# currentsense.net
KiCad netlist of a schematic drawn in EAGLE
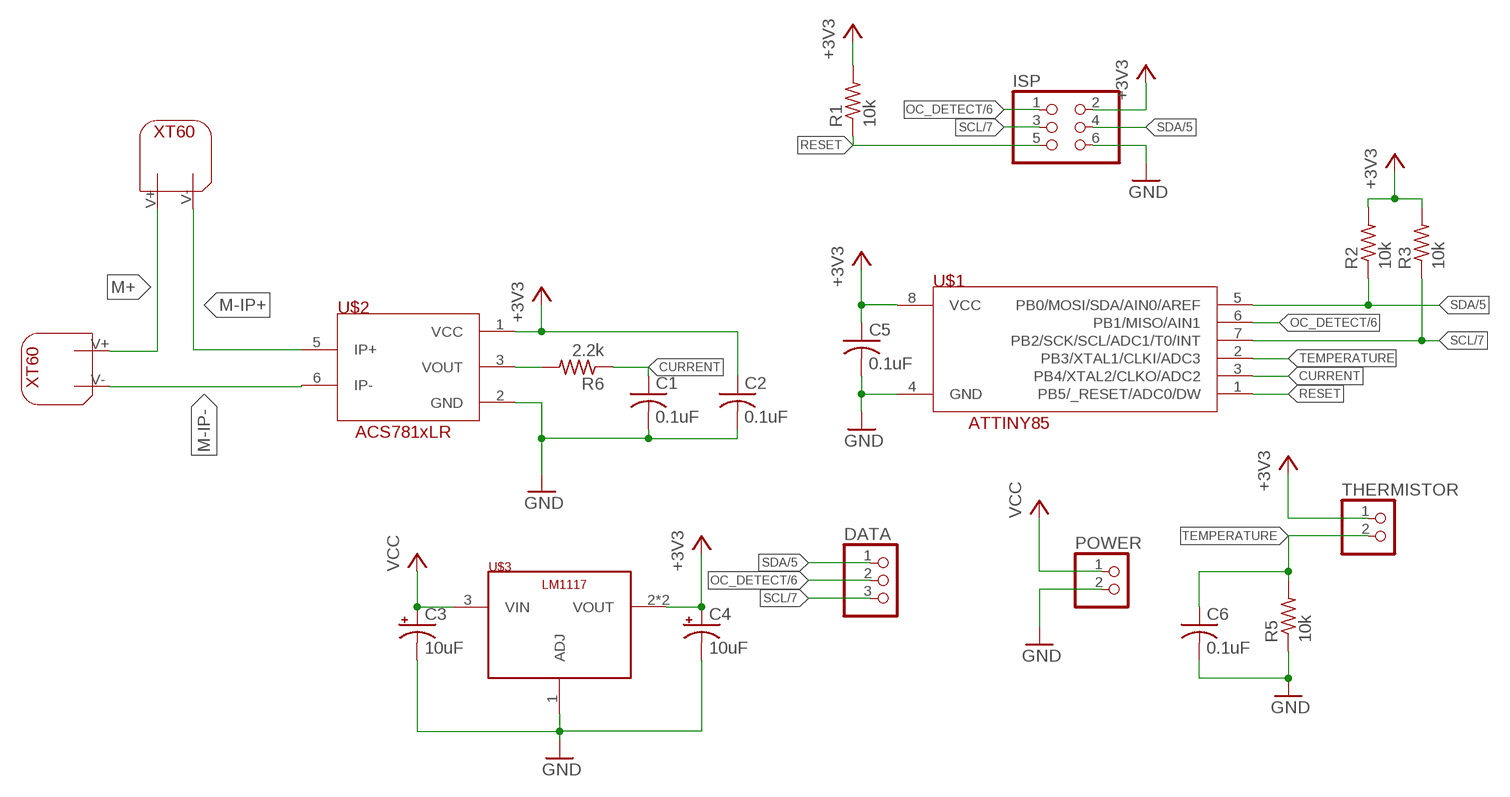
[diagram p0: schematic, sheet 1]

(export (version "E")
  (design (tool "Eeschema 10.0.6"))
  (components
    (comp (ref "C1")
      (value "0.1uF")
      (footprint "eagle-import:C0805")
      (libsource (lib "eagle-import") (part "C-USC0805"))
    )
    (comp (ref "C2")
      (value "0.1uF")
      (footprint "eagle-import:C0805")
      (libsource (lib "eagle-import") (part "C-USC0805"))
    )
    (comp (ref "C3")
      (value "10uF")
      (footprint "eagle-import:E2,5-6")
      (libsource (lib "eagle-import") (part "CPOL-USE2.5-6"))
    )
    (comp (ref "C4")
      (value "10uF")
      (footprint "eagle-import:E2,5-6")
      (libsource (lib "eagle-import") (part "CPOL-USE2.5-6"))
    )
    (comp (ref "C5")
      (value "0.1uF")
      (footprint "eagle-import:C0805")
      (libsource (lib "eagle-import") (part "C-USC0805"))
    )
    (comp (ref "C6")
      (value "0.1uF")
      (footprint "eagle-import:C0805")
      (libsource (lib "eagle-import") (part "C-USC0805"))
    )
    (comp (ref "DATA")
      (value "PINHD-1X3")
      (footprint "eagle-import:1X03")
      (libsource (lib "eagle-import") (part "PINHD-1X3"))
    )
    (comp (ref "ISP")
      (value "PINHD-2X3")
      (footprint "eagle-import:2X03")
      (libsource (lib "eagle-import") (part "PINHD-2X3"))
    )
    (comp (ref "POWER")
      (value "PINHD-1X2")
      (footprint "eagle-import:1X02")
      (libsource (lib "eagle-import") (part "PINHD-1X2"))
    )
    (comp (ref "R1")
      (value "10k")
      (footprint "eagle-import:M0805")
      (libsource (lib "eagle-import") (part "R-US_M0805"))
    )
    (comp (ref "R2")
      (value "10k")
      (footprint "eagle-import:M0805")
      (libsource (lib "eagle-import") (part "R-US_M0805"))
    )
    (comp (ref "R3")
      (value "10k")
      (footprint "eagle-import:M0805")
      (libsource (lib "eagle-import") (part "R-US_M0805"))
    )
    (comp (ref "R5")
      (value "10k")
      (footprint "eagle-import:M0805")
      (libsource (lib "eagle-import") (part "R-US_M0805"))
    )
    (comp (ref "R6")
      (value "2.2k")
      (footprint "eagle-import:M0805")
      (libsource (lib "eagle-import") (part "R-US_M0805"))
    )
    (comp (ref "THERMISTOR")
      (value "PINHD-1X2")
      (footprint "eagle-import:1X02")
      (libsource (lib "eagle-import") (part "PINHD-1X2"))
    )
    (comp (ref "U$1")
      (value "ATTINY85V-10SUR")
      (footprint "eagle-import:SOIC8")
      (libsource (lib "eagle-import") (part "ATTINY85V-10SUR"))
    )
    (comp (ref "U$2")
      (value "ACS781LLRTR-050B-T_M")
      (footprint "eagle-import:7-PSOF-EXTENDED")
      (libsource (lib "eagle-import") (part "ACS781LLRTR-050B-T_M"))
    )
    (comp (ref "U$3")
      (value "LM1117")
      (footprint "eagle-import:SOT223")
      (libsource (lib "eagle-import") (part "LM1117"))
    )
    (comp (ref "U$4")
      (value "XT60-RA")
      (footprint "eagle-import:XT60_RA")
      (libsource (lib "eagle-import") (part "XT60-RA"))
    )
    (comp (ref "U$5")
      (value "XT60-RA")
      (footprint "eagle-import:XT60_RA")
      (libsource (lib "eagle-import") (part "XT60-RA"))
    )
  )
  (nets
    (net (code "1") (name "+3V3") (class "Default")
      (node (ref "C2") (pin "1") (pinfunction "1_1") (pintype "passive"))
      (node (ref "C4") (pin "+") (pinfunction "+_+") (pintype "passive"))
      (node (ref "C5") (pin "1") (pinfunction "1_1") (pintype "passive"))
      (node (ref "ISP") (pin "2") (pinfunction "2_2") (pintype "passive"))
      (node (ref "R1") (pin "2") (pinfunction "2_2") (pintype "passive"))
      (node (ref "R2") (pin "2") (pinfunction "2_2") (pintype "passive"))
      (node (ref "R3") (pin "2") (pinfunction "2_2") (pintype "passive"))
      (node (ref "THERMISTOR") (pin "1") (pinfunction "1_1") (pintype "passive"))
      (node (ref "U$1") (pin "8") (pinfunction "VCC_8") (pintype "power_in"))
      (node (ref "U$2") (pin "1") (pinfunction "VCC_1") (pintype "bidirectional"))
      (node (ref "U$3") (pin "2") (pinfunction "VOUT_2") (pintype "bidirectional"))
      (node (ref "U$3") (pin "4") (pinfunction "VOUT_4") (pintype "bidirectional"))
    )
    (net (code "2") (name "CURRENT") (class "Default")
      (node (ref "C1") (pin "1") (pinfunction "1_1") (pintype "passive"))
      (node (ref "R6") (pin "1") (pinfunction "1_1") (pintype "passive"))
      (node (ref "U$1") (pin "3") (pinfunction "PB4/XTAL2/CLKO/ADC2_3") (pintype "bidirectional"))
    )
    (net (code "3") (name "GND") (class "Default")
      (node (ref "C1") (pin "2") (pinfunction "2_2") (pintype "passive"))
      (node (ref "C2") (pin "2") (pinfunction "2_2") (pintype "passive"))
      (node (ref "C3") (pin "-") (pinfunction "-_-") (pintype "passive"))
      (node (ref "C4") (pin "-") (pinfunction "-_-") (pintype "passive"))
      (node (ref "C5") (pin "2") (pinfunction "2_2") (pintype "passive"))
      (node (ref "C6") (pin "2") (pinfunction "2_2") (pintype "passive"))
      (node (ref "ISP") (pin "6") (pinfunction "6_6") (pintype "passive"))
      (node (ref "POWER") (pin "2") (pinfunction "2_2") (pintype "passive"))
      (node (ref "R5") (pin "1") (pinfunction "1_1") (pintype "passive"))
      (node (ref "U$1") (pin "4") (pinfunction "GND_4") (pintype "power_in"))
      (node (ref "U$2") (pin "2") (pinfunction "GND_2") (pintype "bidirectional"))
      (node (ref "U$3") (pin "1") (pinfunction "ADJ_1") (pintype "bidirectional"))
    )
    (net (code "4") (name "M+") (class "Default")
      (node (ref "U$4") (pin "V+") (pinfunction "V+_V+") (pintype "bidirectional"))
      (node (ref "U$5") (pin "V+") (pinfunction "V+_V+") (pintype "bidirectional"))
    )
    (net (code "5") (name "M-IP+") (class "Default")
      (node (ref "U$2") (pin "5") (pinfunction "IP+_5") (pintype "bidirectional"))
      (node (ref "U$4") (pin "V-") (pinfunction "V-_V-") (pintype "bidirectional"))
    )
    (net (code "6") (name "M-IP-") (class "Default")
      (node (ref "U$2") (pin "6") (pinfunction "IP-_6") (pintype "bidirectional"))
      (node (ref "U$5") (pin "V-") (pinfunction "V-_V-") (pintype "bidirectional"))
    )
    (net (code "7") (name "Net-(U$2-VOUT)") (class "Default")
      (node (ref "R6") (pin "2") (pinfunction "2_2") (pintype "passive"))
      (node (ref "U$2") (pin "3") (pinfunction "VOUT_3") (pintype "bidirectional"))
    )
    (net (code "8") (name "OC_DETECT{slash}6") (class "Default")
      (node (ref "DATA") (pin "2") (pinfunction "2_2") (pintype "passive"))
      (node (ref "ISP") (pin "1") (pinfunction "1_1") (pintype "passive"))
      (node (ref "U$1") (pin "6") (pinfunction "PB1/MISO/AIN1_6") (pintype "bidirectional"))
    )
    (net (code "9") (name "RESET") (class "Default")
      (node (ref "ISP") (pin "5") (pinfunction "5_5") (pintype "passive"))
      (node (ref "R1") (pin "1") (pinfunction "1_1") (pintype "passive"))
      (node (ref "U$1") (pin "1") (pinfunction "PB5/_RESET/ADC0/DW_1") (pintype "bidirectional"))
    )
    (net (code "10") (name "SCL{slash}7") (class "Default")
      (node (ref "DATA") (pin "3") (pinfunction "3_3") (pintype "passive"))
      (node (ref "ISP") (pin "3") (pinfunction "3_3") (pintype "passive"))
      (node (ref "R3") (pin "1") (pinfunction "1_1") (pintype "passive"))
      (node (ref "U$1") (pin "7") (pinfunction "PB2/SCK/SCL/ADC1/T0/INT_7") (pintype "bidirectional"))
    )
    (net (code "11") (name "SDA{slash}5") (class "Default")
      (node (ref "DATA") (pin "1") (pinfunction "1_1") (pintype "passive"))
      (node (ref "ISP") (pin "4") (pinfunction "4_4") (pintype "passive"))
      (node (ref "R2") (pin "1") (pinfunction "1_1") (pintype "passive"))
      (node (ref "U$1") (pin "5") (pinfunction "PB0/MOSI/SDA/AIN0/AREF_5") (pintype "bidirectional"))
    )
    (net (code "12") (name "TEMPERATURE") (class "Default")
      (node (ref "C6") (pin "1") (pinfunction "1_1") (pintype "passive"))
      (node (ref "R5") (pin "2") (pinfunction "2_2") (pintype "passive"))
      (node (ref "THERMISTOR") (pin "2") (pinfunction "2_2") (pintype "passive"))
      (node (ref "U$1") (pin "2") (pinfunction "PB3/XTAL1/CLKI/ADC3_2") (pintype "bidirectional"))
    )
    (net (code "13") (name "VCC") (class "Default")
      (node (ref "C3") (pin "+") (pinfunction "+_+") (pintype "passive"))
      (node (ref "POWER") (pin "1") (pinfunction "1_1") (pintype "passive"))
      (node (ref "U$3") (pin "3") (pinfunction "VIN_3") (pintype "bidirectional"))
    )
  )
)
